# BATT_FLEX9.net
KiCad netlist of a schematic drawn in EAGLE
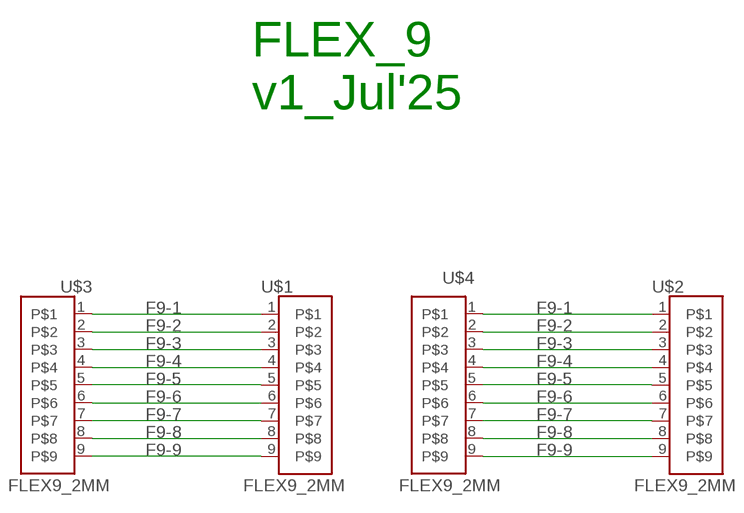
[diagram p0: schematic, sheet 1]

(export (version "E")
  (design (tool "Eeschema 10.0.6"))
  (components
    (comp (ref "U$1")
      (value "FLEX9_2MM")
      (footprint "eagle-import:FLEX9_2MM")
      (libsource (lib "eagle-import") (part "FLEX9_2MM"))
    )
    (comp (ref "U$2")
      (value "FLEX9_2MM")
      (footprint "eagle-import:FLEX9_2MM")
      (libsource (lib "eagle-import") (part "FLEX9_2MM"))
    )
    (comp (ref "U$3")
      (value "FLEX9_2MM")
      (footprint "eagle-import:FLEX9_2MM")
      (libsource (lib "eagle-import") (part "FLEX9_2MM"))
    )
    (comp (ref "U$4")
      (value "FLEX9_2MM")
      (footprint "eagle-import:FLEX9_2MM")
      (libsource (lib "eagle-import") (part "FLEX9_2MM"))
    )
  )
  (nets
    (net (code "1") (name "/F9-1") (class "Default")
      (node (ref "U$1") (pin "1") (pinfunction "P$1_1") (pintype "bidirectional"))
      (node (ref "U$2") (pin "1") (pinfunction "P$1_1") (pintype "bidirectional"))
      (node (ref "U$3") (pin "1") (pinfunction "P$1_1") (pintype "bidirectional"))
      (node (ref "U$4") (pin "1") (pinfunction "P$1_1") (pintype "bidirectional"))
    )
    (net (code "2") (name "/F9-2") (class "Default")
      (node (ref "U$1") (pin "2") (pinfunction "P$2_2") (pintype "bidirectional"))
      (node (ref "U$2") (pin "2") (pinfunction "P$2_2") (pintype "bidirectional"))
      (node (ref "U$3") (pin "2") (pinfunction "P$2_2") (pintype "bidirectional"))
      (node (ref "U$4") (pin "2") (pinfunction "P$2_2") (pintype "bidirectional"))
    )
    (net (code "3") (name "/F9-3") (class "Default")
      (node (ref "U$1") (pin "3") (pinfunction "P$3_3") (pintype "bidirectional"))
      (node (ref "U$2") (pin "3") (pinfunction "P$3_3") (pintype "bidirectional"))
      (node (ref "U$3") (pin "3") (pinfunction "P$3_3") (pintype "bidirectional"))
      (node (ref "U$4") (pin "3") (pinfunction "P$3_3") (pintype "bidirectional"))
    )
    (net (code "4") (name "/F9-4") (class "Default")
      (node (ref "U$1") (pin "4") (pinfunction "P$4_4") (pintype "bidirectional"))
      (node (ref "U$2") (pin "4") (pinfunction "P$4_4") (pintype "bidirectional"))
      (node (ref "U$3") (pin "4") (pinfunction "P$4_4") (pintype "bidirectional"))
      (node (ref "U$4") (pin "4") (pinfunction "P$4_4") (pintype "bidirectional"))
    )
    (net (code "5") (name "/F9-5") (class "Default")
      (node (ref "U$1") (pin "5") (pinfunction "P$5_5") (pintype "bidirectional"))
      (node (ref "U$2") (pin "5") (pinfunction "P$5_5") (pintype "bidirectional"))
      (node (ref "U$3") (pin "5") (pinfunction "P$5_5") (pintype "bidirectional"))
      (node (ref "U$4") (pin "5") (pinfunction "P$5_5") (pintype "bidirectional"))
    )
    (net (code "6") (name "/F9-6") (class "Default")
      (node (ref "U$1") (pin "6") (pinfunction "P$6_6") (pintype "bidirectional"))
      (node (ref "U$2") (pin "6") (pinfunction "P$6_6") (pintype "bidirectional"))
      (node (ref "U$3") (pin "6") (pinfunction "P$6_6") (pintype "bidirectional"))
      (node (ref "U$4") (pin "6") (pinfunction "P$6_6") (pintype "bidirectional"))
    )
    (net (code "7") (name "/F9-7") (class "Default")
      (node (ref "U$1") (pin "7") (pinfunction "P$7_7") (pintype "bidirectional"))
      (node (ref "U$2") (pin "7") (pinfunction "P$7_7") (pintype "bidirectional"))
      (node (ref "U$3") (pin "7") (pinfunction "P$7_7") (pintype "bidirectional"))
      (node (ref "U$4") (pin "7") (pinfunction "P$7_7") (pintype "bidirectional"))
    )
    (net (code "8") (name "/F9-8") (class "Default")
      (node (ref "U$1") (pin "8") (pinfunction "P$8_8") (pintype "bidirectional"))
      (node (ref "U$2") (pin "8") (pinfunction "P$8_8") (pintype "bidirectional"))
      (node (ref "U$3") (pin "8") (pinfunction "P$8_8") (pintype "bidirectional"))
      (node (ref "U$4") (pin "8") (pinfunction "P$8_8") (pintype "bidirectional"))
    )
    (net (code "9") (name "/F9-9") (class "Default")
      (node (ref "U$1") (pin "9") (pinfunction "P$9_9") (pintype "bidirectional"))
      (node (ref "U$2") (pin "9") (pinfunction "P$9_9") (pintype "bidirectional"))
      (node (ref "U$3") (pin "9") (pinfunction "P$9_9") (pintype "bidirectional"))
      (node (ref "U$4") (pin "9") (pinfunction "P$9_9") (pintype "bidirectional"))
    )
  )
)
